# SCH_MODULO_GPS.net
KiCad netlist of a schematic drawn in Altium Designer
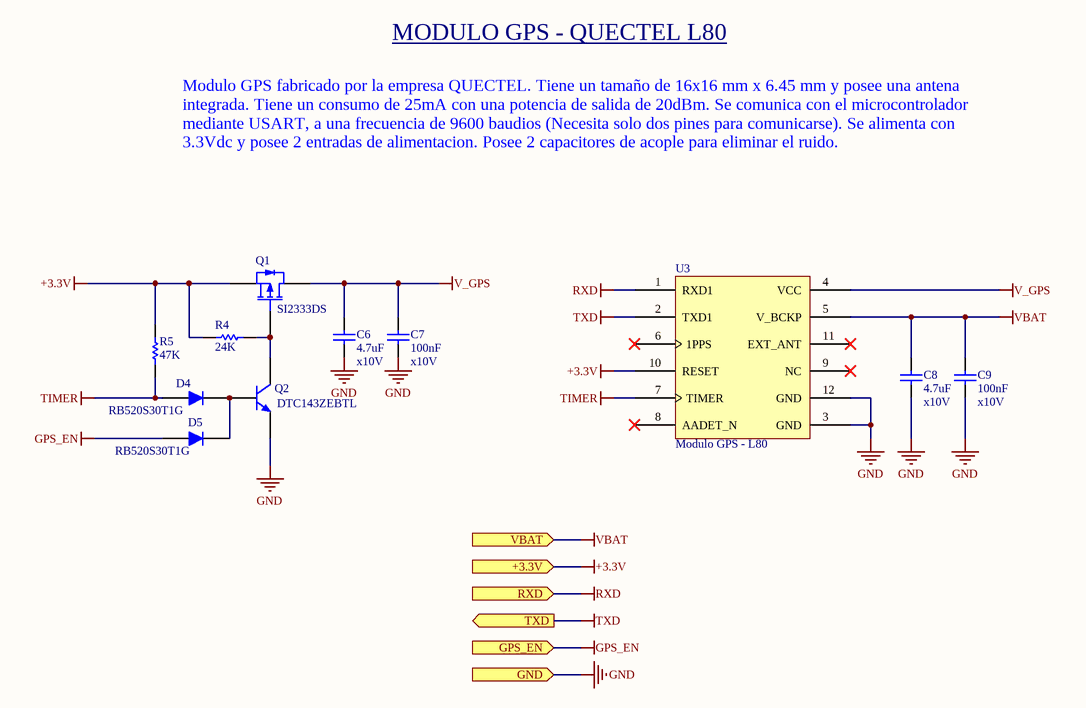
[diagram p0: SCH_MODULO_GPS.SchDoc]

(export (version "E")
  (design (tool "Eeschema 10.0.6"))
  (components
    (comp (ref "C6")
      (value "4.7uF")
      (footprint "RAD-0.3")
      (description "Capacitor")
      (fields
        (field (name "VOLTAGE") "x10V")
        (field (name "Comment") "Capacitor - Común")
        (field (name "PUBLISHER") "Altium Limited")
      )
      (libsource (lib "LIB_COLLAR") (part "Capacitor - Común"))
    )
    (comp (ref "C7")
      (value "100nF")
      (footprint "RAD-0.3")
      (description "Capacitor")
      (fields
        (field (name "VOLTAGE") "x10V")
        (field (name "Comment") "Capacitor - Común")
        (field (name "PUBLISHER") "Altium Limited")
      )
      (libsource (lib "LIB_COLLAR") (part "Capacitor - Común"))
    )
    (comp (ref "C8")
      (value "4.7uF")
      (footprint "RAD-0.3")
      (description "Capacitor")
      (fields
        (field (name "VOLTAGE") "x10V")
        (field (name "Comment") "Capacitor - Común")
        (field (name "PUBLISHER") "Altium Limited")
      )
      (libsource (lib "LIB_COLLAR") (part "Capacitor - Común"))
    )
    (comp (ref "C9")
      (value "100nF")
      (footprint "RAD-0.3")
      (description "Capacitor")
      (fields
        (field (name "VOLTAGE") "x10V")
        (field (name "Comment") "Capacitor - Común")
        (field (name "PUBLISHER") "Altium Limited")
      )
      (libsource (lib "LIB_COLLAR") (part "Capacitor - Común"))
    )
    (comp (ref "D4")
      (value "RB520S30T1G")
      (footprint "SMC")
      (description "Default Diode")
      (fields (field (name "PUBLISHER") "Altium Limited"))
      (libsource (lib "LIB_COLLAR") (part "Diodo - Común"))
    )
    (comp (ref "D5")
      (value "RB520S30T1G")
      (footprint "SMC")
      (description "Default Diode")
      (fields (field (name "PUBLISHER") "Altium Limited"))
      (libsource (lib "LIB_COLLAR") (part "Diodo - Común"))
    )
    (comp (ref "Q1")
      (value "SI2333DS")
      (footprint "E3")
      (description "P-Channel MOSFET")
      (fields (field (name "PUBLISHER") "Altium Limited"))
      (libsource (lib "LIB_COLLAR") (part "Transistor - MOS/P"))
    )
    (comp (ref "Q2")
      (value "DTC143ZEBTL")
      (footprint "TO-92A")
      (description "NPN General Purpose Amplifier")
      (fields (field (name "PUBLISHER") "Altium Limited"))
      (libsource (lib "LIB_COLLAR") (part "Transistor - NPN"))
    )
    (comp (ref "R4")
      (value "24K")
      (footprint "AXIAL-0.5")
      (description "Semiconductor Resistor")
      (fields (field (name "Comment") "Resistencia - Común") (field (name "PUBLISHER") "Altium Limited"))
      (libsource (lib "LIB_COLLAR") (part "Resistencia - Común"))
    )
    (comp (ref "R5")
      (value "47K")
      (footprint "AXIAL-0.5")
      (description "Semiconductor Resistor")
      (fields (field (name "Comment") "Resistencia - Común") (field (name "PUBLISHER") "Altium Limited"))
      (libsource (lib "LIB_COLLAR") (part "Resistencia - Común"))
    )
    (comp (ref "U3")
      (value "Modulo GPS - L80")
      (description "QUECTEL L80")
      (libsource (lib "LIB_COLLAR") (part "Modulo GPS - L80"))
    )
  )
  (nets
    (net (code "1") (name "+3.3V") (class "Default")
      (node (ref "Q1") (pin "3") (pinfunction "S_3") (pintype "passive"))
      (node (ref "R4") (pin "1") (pinfunction "1_1") (pintype "passive"))
      (node (ref "R5") (pin "2") (pinfunction "2_2") (pintype "passive"))
      (node (ref "U3") (pin "10") (pinfunction "RESET_10") (pintype "passive"))
    )
    (net (code "2") (name "GND") (class "Default")
      (node (ref "C6") (pin "1") (pinfunction "1_1") (pintype "passive"))
      (node (ref "C7") (pin "1") (pinfunction "1_1") (pintype "passive"))
      (node (ref "C8") (pin "1") (pinfunction "1_1") (pintype "passive"))
      (node (ref "C9") (pin "1") (pinfunction "1_1") (pintype "passive"))
      (node (ref "Q2") (pin "1") (pinfunction "E_1") (pintype "passive"))
      (node (ref "U3") (pin "12") (pinfunction "GND_12") (pintype "passive"))
      (node (ref "U3") (pin "3") (pinfunction "GND_3") (pintype "passive"))
    )
    (net (code "3") (name "GPS_EN") (class "Default")
      (node (ref "D5") (pin "1") (pinfunction "A_1") (pintype "passive"))
    )
    (net (code "4") (name "Net-(D4-K)") (class "Default")
      (node (ref "D4") (pin "2") (pinfunction "K_2") (pintype "passive"))
      (node (ref "D5") (pin "2") (pinfunction "K_2") (pintype "passive"))
      (node (ref "Q2") (pin "2") (pinfunction "B_2") (pintype "passive"))
    )
    (net (code "5") (name "Net-(Q1-G)") (class "Default")
      (node (ref "Q1") (pin "2") (pinfunction "G_2") (pintype "passive"))
      (node (ref "Q2") (pin "3") (pinfunction "C_3") (pintype "passive"))
      (node (ref "R4") (pin "2") (pinfunction "2_2") (pintype "passive"))
    )
    (net (code "6") (name "RXD") (class "Default")
      (node (ref "U3") (pin "1") (pinfunction "RXD1_1") (pintype "passive"))
    )
    (net (code "7") (name "TIMER") (class "Default")
      (node (ref "D4") (pin "1") (pinfunction "A_1") (pintype "passive"))
      (node (ref "R5") (pin "1") (pinfunction "1_1") (pintype "passive"))
      (node (ref "U3") (pin "7") (pinfunction "TIMER_7") (pintype "passive"))
    )
    (net (code "8") (name "TXD") (class "Default")
      (node (ref "U3") (pin "2") (pinfunction "TXD1_2") (pintype "passive"))
    )
    (net (code "9") (name "VBAT") (class "Default")
      (node (ref "C8") (pin "2") (pinfunction "2_2") (pintype "passive"))
      (node (ref "C9") (pin "2") (pinfunction "2_2") (pintype "passive"))
      (node (ref "U3") (pin "5") (pinfunction "V_BCKP_5") (pintype "passive"))
    )
    (net (code "10") (name "V_GPS") (class "Default")
      (node (ref "C6") (pin "2") (pinfunction "2_2") (pintype "passive"))
      (node (ref "C7") (pin "2") (pinfunction "2_2") (pintype "passive"))
      (node (ref "Q1") (pin "1") (pinfunction "D_1") (pintype "passive"))
      (node (ref "U3") (pin "4") (pinfunction "VCC_4") (pintype "passive"))
    )
    (net (code "11") (name "unconnected-(U3-1PPS-Pad6)") (class "Default")
      (node (ref "U3") (pin "6") (pinfunction "1PPS_6") (pintype "passive+no_connect"))
    )
    (net (code "12") (name "unconnected-(U3-AADET_N-Pad8)") (class "Default")
      (node (ref "U3") (pin "8") (pinfunction "AADET_N_8") (pintype "passive+no_connect"))
    )
    (net (code "13") (name "unconnected-(U3-EXT_ANT-Pad11)") (class "Default")
      (node (ref "U3") (pin "11") (pinfunction "EXT_ANT_11") (pintype "passive+no_connect"))
    )
    (net (code "14") (name "unconnected-(U3-NC-Pad9)") (class "Default")
      (node (ref "U3") (pin "9") (pinfunction "NC_9") (pintype "passive+no_connect"))
    )
  )
)
